# pidshield-mk-3_1.net
KiCad netlist of a schematic drawn in EAGLE
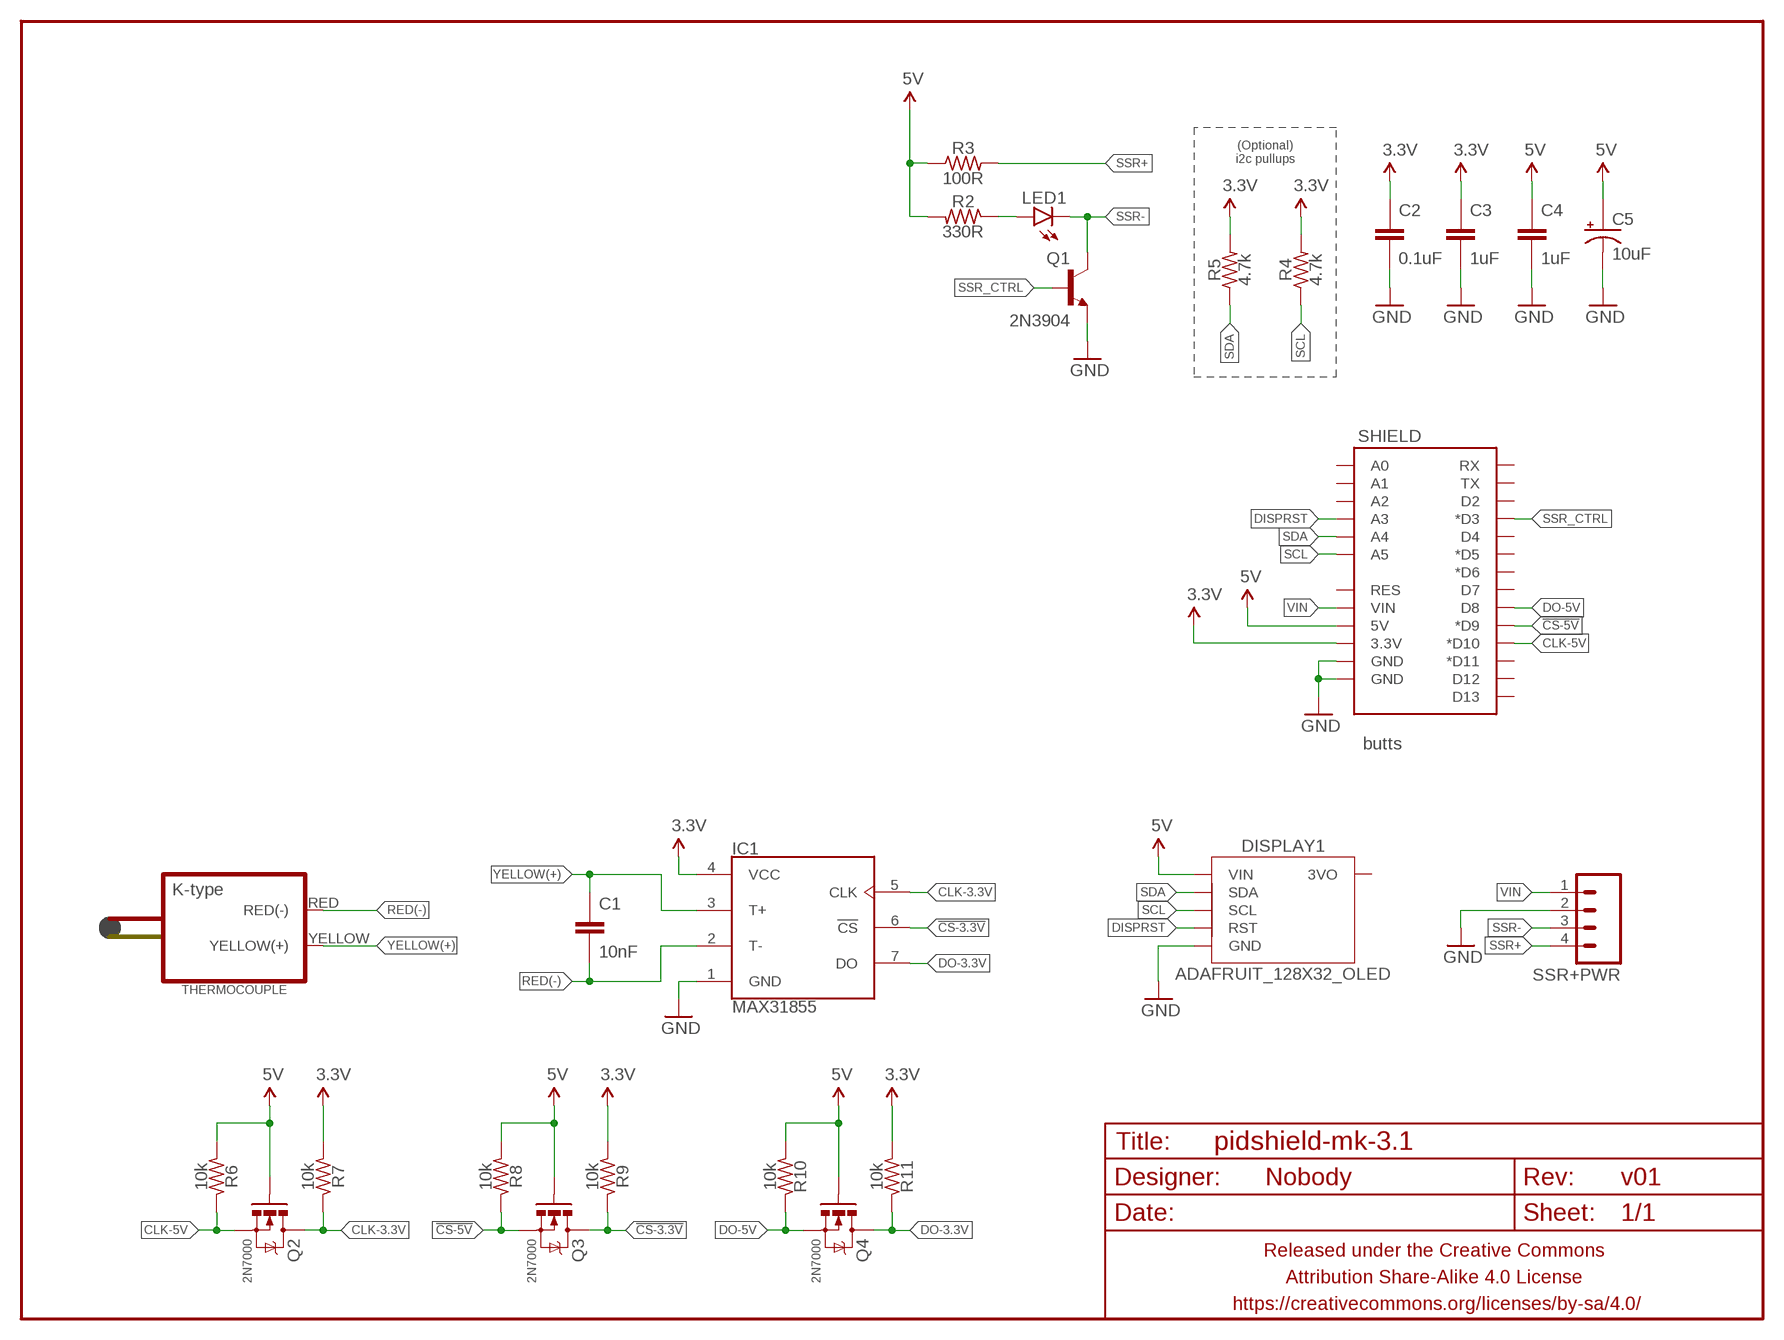
[diagram p0: schematic, sheet 1]

(export (version "E")
  (design (tool "Eeschema 10.0.6"))
  (components
    (comp (ref "C1")
      (value "10nF")
      (footprint "eagle-import:C0805")
      (libsource (lib "eagle-import") (part "CAPACITOR-CERAMICC0805"))
    )
    (comp (ref "C2")
      (value "0.1uF")
      (footprint "eagle-import:C025-024X044")
      (libsource (lib "eagle-import") (part "CAPACITOR-CERAMIC025-024X044"))
    )
    (comp (ref "C3")
      (value "1uF")
      (footprint "eagle-import:C025-024X044")
      (libsource (lib "eagle-import") (part "CAPACITOR-CERAMIC025-024X044"))
    )
    (comp (ref "C4")
      (value "1uF")
      (footprint "eagle-import:C025-024X044")
      (libsource (lib "eagle-import") (part "CAPACITOR-CERAMIC025-024X044"))
    )
    (comp (ref "C5")
      (value "10uF")
      (footprint "eagle-import:E2,5-6")
      (libsource (lib "eagle-import") (part "CAPACITOR-POLARIZEDE2.5-6"))
    )
    (comp (ref "DISPLAY1")
      (value "ADAFRUIT_128X32_OLED")
      (footprint "eagle-import:ADAFRUIT_128X32_OLED_I2C_CLOSER_NOTITLE")
      (libsource (lib "eagle-import") (part "ADAFRUIT_128X32_OLED_I2CNOTITLE"))
    )
    (comp (ref "FRAME1")
      (value "FRAME-LETTERNO_PACKAGE")
      (footprint "eagle-import:DUMMY")
      (fields (field (name "DESIGNER") "Nobody"))
      (libsource (lib "eagle-import") (part "FRAME-LETTERNO_PACKAGE"))
    )
    (comp (ref "IC1")
      (value "MAX31855")
      (footprint "eagle-import:SOIC127P600X175-8N")
      (libsource (lib "eagle-import") (part "MAX31855SOIC"))
    )
    (comp (ref "LED1")
      (value "LED3MM-LESS")
      (footprint "eagle-import:LED3MM-LESSSILK")
      (libsource (lib "eagle-import") (part "LED3MM-LESS"))
    )
    (comp (ref "Q1")
      (value "2N3904")
      (footprint "eagle-import:TO-92-AMMO")
      (libsource (lib "eagle-import") (part "TRANSISTOR_NPNTO-92-AMMO-EBC"))
    )
    (comp (ref "Q2")
      (value "2N7000")
      (footprint "eagle-import:TO-92-AMMO")
      (libsource (lib "eagle-import") (part "MOSFET-NCHANNEL2N7000-AMMO"))
    )
    (comp (ref "Q3")
      (value "2N7000")
      (footprint "eagle-import:TO-92-AMMO")
      (libsource (lib "eagle-import") (part "MOSFET-NCHANNEL2N7000-AMMO"))
    )
    (comp (ref "Q4")
      (value "2N7000")
      (footprint "eagle-import:TO-92-AMMO")
      (libsource (lib "eagle-import") (part "MOSFET-NCHANNEL2N7000-AMMO"))
    )
    (comp (ref "R2")
      (value "330R")
      (footprint "eagle-import:RESISTOR-AXIAL-PTH-7.62MM")
      (libsource (lib "eagle-import") (part "RESISTORPTH-AXIAL-7.62MM"))
    )
    (comp (ref "R3")
      (value "100R")
      (footprint "eagle-import:RESISTOR-AXIAL-PTH-7.62MM")
      (libsource (lib "eagle-import") (part "RESISTORPTH-AXIAL-7.62MM"))
    )
    (comp (ref "R4")
      (value "4.7k")
      (footprint "eagle-import:RESISTOR-AXIAL-PTH-7.62MM")
      (libsource (lib "eagle-import") (part "RESISTORPTH-AXIAL-7.62MM"))
    )
    (comp (ref "R5")
      (value "4.7k")
      (footprint "eagle-import:RESISTOR-AXIAL-PTH-7.62MM")
      (libsource (lib "eagle-import") (part "RESISTORPTH-AXIAL-7.62MM"))
    )
    (comp (ref "R6")
      (value "10k")
      (footprint "eagle-import:RESISTOR-AXIAL-PTH-7.62MM")
      (libsource (lib "eagle-import") (part "RESISTORPTH-AXIAL-7.62MM"))
    )
    (comp (ref "R7")
      (value "10k")
      (footprint "eagle-import:RESISTOR-AXIAL-PTH-7.62MM")
      (libsource (lib "eagle-import") (part "RESISTORPTH-AXIAL-7.62MM"))
    )
    (comp (ref "R8")
      (value "10k")
      (footprint "eagle-import:RESISTOR-AXIAL-PTH-7.62MM")
      (libsource (lib "eagle-import") (part "RESISTORPTH-AXIAL-7.62MM"))
    )
    (comp (ref "R9")
      (value "10k")
      (footprint "eagle-import:RESISTOR-AXIAL-PTH-7.62MM")
      (libsource (lib "eagle-import") (part "RESISTORPTH-AXIAL-7.62MM"))
    )
    (comp (ref "R10")
      (value "10k")
      (footprint "eagle-import:RESISTOR-AXIAL-PTH-7.62MM")
      (libsource (lib "eagle-import") (part "RESISTORPTH-AXIAL-7.62MM"))
    )
    (comp (ref "R11")
      (value "10k")
      (footprint "eagle-import:RESISTOR-AXIAL-PTH-7.62MM")
      (libsource (lib "eagle-import") (part "RESISTORPTH-AXIAL-7.62MM"))
    )
    (comp (ref "SHIELD")
      (value "butts")
      (footprint "eagle-import:ARDUINO_SHIELD_SMALLER_NEKKID")
      (libsource (lib "eagle-import") (part "ARDUINO_SHIELD_SMALLERNEKKID"))
    )
    (comp (ref "SSR+PWR")
      (value "M04JST_XH_RA")
      (footprint "eagle-import:JST-4-XH-RA-PTH")
      (libsource (lib "eagle-import") (part "M04JST_XH_RA"))
    )
    (comp (ref "THERMOCOUPLE")
      (value "THERMOCOUPLE-CONNECTORMINI-PCB")
      (footprint "eagle-import:PCC-SMP")
      (libsource (lib "eagle-import") (part "THERMOCOUPLE-CONNECTORMINI-PCB"))
    )
  )
  (nets
    (net (code "1") (name "/~{CS-3.3V}") (class "Default")
      (node (ref "IC1") (pin "6") (pinfunction "~{CS}_6") (pintype "input"))
      (node (ref "Q3") (pin "3") (pinfunction "D_3") (pintype "passive"))
      (node (ref "R9") (pin "P$1") (pinfunction "1_P$1") (pintype "passive"))
    )
    (net (code "2") (name "/~{CS-5V}") (class "Default")
      (node (ref "Q3") (pin "1") (pinfunction "S_1") (pintype "passive"))
      (node (ref "R8") (pin "P$1") (pinfunction "1_P$1") (pintype "passive"))
      (node (ref "SHIELD") (pin "D9") (pinfunction "*D9_D9") (pintype "bidirectional"))
    )
    (net (code "3") (name "3.3V") (class "Default")
      (node (ref "C2") (pin "1") (pinfunction "1_1") (pintype "passive"))
      (node (ref "C3") (pin "1") (pinfunction "1_1") (pintype "passive"))
      (node (ref "IC1") (pin "4") (pinfunction "VCC_4") (pintype "power_in"))
      (node (ref "R11") (pin "P$2") (pinfunction "2_P$2") (pintype "passive"))
      (node (ref "R4") (pin "P$2") (pinfunction "2_P$2") (pintype "passive"))
      (node (ref "R5") (pin "P$2") (pinfunction "2_P$2") (pintype "passive"))
      (node (ref "R7") (pin "P$2") (pinfunction "2_P$2") (pintype "passive"))
      (node (ref "R9") (pin "P$2") (pinfunction "2_P$2") (pintype "passive"))
      (node (ref "SHIELD") (pin "3.3V") (pinfunction "3.3V_3.3V") (pintype "bidirectional"))
    )
    (net (code "4") (name "5V") (class "Default")
      (node (ref "C4") (pin "1") (pinfunction "1_1") (pintype "passive"))
      (node (ref "C5") (pin "+") (pinfunction "+_+") (pintype "passive"))
      (node (ref "DISPLAY1") (pin "VIN") (pinfunction "VIN_VIN") (pintype "bidirectional"))
      (node (ref "Q2") (pin "2") (pinfunction "G_2") (pintype "passive"))
      (node (ref "Q3") (pin "2") (pinfunction "G_2") (pintype "passive"))
      (node (ref "Q4") (pin "2") (pinfunction "G_2") (pintype "passive"))
      (node (ref "R10") (pin "P$2") (pinfunction "2_P$2") (pintype "passive"))
      (node (ref "R2") (pin "P$2") (pinfunction "2_P$2") (pintype "passive"))
      (node (ref "R3") (pin "P$1") (pinfunction "1_P$1") (pintype "passive"))
      (node (ref "R6") (pin "P$2") (pinfunction "2_P$2") (pintype "passive"))
      (node (ref "R8") (pin "P$2") (pinfunction "2_P$2") (pintype "passive"))
      (node (ref "SHIELD") (pin "5V") (pinfunction "5V_5V") (pintype "bidirectional"))
    )
    (net (code "5") (name "CLK-3.3V") (class "Default")
      (node (ref "IC1") (pin "5") (pinfunction "CLK_5") (pintype "input"))
      (node (ref "Q2") (pin "3") (pinfunction "D_3") (pintype "passive"))
      (node (ref "R7") (pin "P$1") (pinfunction "1_P$1") (pintype "passive"))
    )
    (net (code "6") (name "CLK-5V") (class "Default")
      (node (ref "Q2") (pin "1") (pinfunction "S_1") (pintype "passive"))
      (node (ref "R6") (pin "P$1") (pinfunction "1_P$1") (pintype "passive"))
      (node (ref "SHIELD") (pin "D10") (pinfunction "*D10_D10") (pintype "bidirectional"))
    )
    (net (code "7") (name "DISPRST") (class "Default")
      (node (ref "DISPLAY1") (pin "RST") (pinfunction "RST_RST") (pintype "bidirectional"))
      (node (ref "SHIELD") (pin "A3") (pinfunction "A3_A3") (pintype "bidirectional"))
    )
    (net (code "8") (name "DO-3.3V") (class "Default")
      (node (ref "IC1") (pin "7") (pinfunction "DO_7") (pintype "output"))
      (node (ref "Q4") (pin "3") (pinfunction "D_3") (pintype "passive"))
      (node (ref "R11") (pin "P$1") (pinfunction "1_P$1") (pintype "passive"))
    )
    (net (code "9") (name "DO-5V") (class "Default")
      (node (ref "Q4") (pin "1") (pinfunction "S_1") (pintype "passive"))
      (node (ref "R10") (pin "P$1") (pinfunction "1_P$1") (pintype "passive"))
      (node (ref "SHIELD") (pin "D8") (pinfunction "D8_D8") (pintype "bidirectional"))
    )
    (net (code "10") (name "GND") (class "Default")
      (node (ref "C2") (pin "2") (pinfunction "2_2") (pintype "passive"))
      (node (ref "C3") (pin "2") (pinfunction "2_2") (pintype "passive"))
      (node (ref "C4") (pin "2") (pinfunction "2_2") (pintype "passive"))
      (node (ref "C5") (pin "-") (pinfunction "-_-") (pintype "passive"))
      (node (ref "DISPLAY1") (pin "GND") (pinfunction "GND_GND") (pintype "bidirectional"))
      (node (ref "IC1") (pin "1") (pinfunction "GND_1") (pintype "power_in"))
      (node (ref "Q1") (pin "1") (pinfunction "E_1") (pintype "passive"))
      (node (ref "SHIELD") (pin "GND@0") (pinfunction "GND_GND@0") (pintype "bidirectional"))
      (node (ref "SHIELD") (pin "GND@1") (pinfunction "GND_GND@1") (pintype "bidirectional"))
      (node (ref "SSR+PWR") (pin "2") (pinfunction "2_2") (pintype "passive"))
    )
    (net (code "11") (name "Net-(R2-1)") (class "Default")
      (node (ref "LED1") (pin "A") (pinfunction "A_A") (pintype "passive"))
      (node (ref "R2") (pin "P$1") (pinfunction "1_P$1") (pintype "passive"))
    )
    (net (code "12") (name "RED(-)") (class "Default")
      (node (ref "C1") (pin "2") (pinfunction "2_2") (pintype "passive"))
      (node (ref "IC1") (pin "2") (pinfunction "T-_2") (pintype "input"))
      (node (ref "THERMOCOUPLE") (pin "RED") (pinfunction "RED(-)_RED") (pintype "bidirectional"))
    )
    (net (code "13") (name "SCL") (class "Default")
      (node (ref "DISPLAY1") (pin "SCL") (pinfunction "SCL_SCL") (pintype "bidirectional"))
      (node (ref "R4") (pin "P$1") (pinfunction "1_P$1") (pintype "passive"))
      (node (ref "SHIELD") (pin "A5") (pinfunction "A5_A5") (pintype "bidirectional"))
    )
    (net (code "14") (name "SDA") (class "Default")
      (node (ref "DISPLAY1") (pin "SDA") (pinfunction "SDA_SDA") (pintype "bidirectional"))
      (node (ref "R5") (pin "P$1") (pinfunction "1_P$1") (pintype "passive"))
      (node (ref "SHIELD") (pin "A4") (pinfunction "A4_A4") (pintype "bidirectional"))
    )
    (net (code "15") (name "SSR+") (class "Default")
      (node (ref "R3") (pin "P$2") (pinfunction "2_P$2") (pintype "passive"))
      (node (ref "SSR+PWR") (pin "4") (pinfunction "4_4") (pintype "passive"))
    )
    (net (code "16") (name "SSR-") (class "Default")
      (node (ref "LED1") (pin "K") (pinfunction "C_K") (pintype "passive"))
      (node (ref "Q1") (pin "3") (pinfunction "C_3") (pintype "passive"))
      (node (ref "SSR+PWR") (pin "3") (pinfunction "3_3") (pintype "passive"))
    )
    (net (code "17") (name "SSR_CTRL") (class "Default")
      (node (ref "Q1") (pin "2") (pinfunction "B_2") (pintype "passive"))
      (node (ref "SHIELD") (pin "D3") (pinfunction "*D3_D3") (pintype "bidirectional"))
    )
    (net (code "18") (name "VIN") (class "Default")
      (node (ref "SHIELD") (pin "VIN") (pinfunction "VIN_VIN") (pintype "bidirectional"))
      (node (ref "SSR+PWR") (pin "1") (pinfunction "1_1") (pintype "passive"))
    )
    (net (code "19") (name "YELLOW(+)") (class "Default")
      (node (ref "C1") (pin "1") (pinfunction "1_1") (pintype "passive"))
      (node (ref "IC1") (pin "3") (pinfunction "T+_3") (pintype "input"))
      (node (ref "THERMOCOUPLE") (pin "YELLOW") (pinfunction "YELLOW(+)_YELLOW") (pintype "bidirectional"))
    )
    (net (code "20") (name "unconnected-(DISPLAY1-Pad3VO)") (class "Default")
      (node (ref "DISPLAY1") (pin "3VO") (pinfunction "3VO_3VO") (pintype "bidirectional"))
    )
    (net (code "21") (name "unconnected-(SHIELD-*D5-PadD5)") (class "Default")
      (node (ref "SHIELD") (pin "D5") (pinfunction "*D5_D5") (pintype "bidirectional"))
    )
    (net (code "22") (name "unconnected-(SHIELD-*D6-PadD6)") (class "Default")
      (node (ref "SHIELD") (pin "D6") (pinfunction "*D6_D6") (pintype "bidirectional"))
    )
    (net (code "23") (name "unconnected-(SHIELD-*D11-PadD11)") (class "Default")
      (node (ref "SHIELD") (pin "D11") (pinfunction "*D11_D11") (pintype "bidirectional"))
    )
    (net (code "24") (name "unconnected-(SHIELD-PadA0)") (class "Default")
      (node (ref "SHIELD") (pin "A0") (pinfunction "A0_A0") (pintype "bidirectional"))
    )
    (net (code "25") (name "unconnected-(SHIELD-PadA1)") (class "Default")
      (node (ref "SHIELD") (pin "A1") (pinfunction "A1_A1") (pintype "bidirectional"))
    )
    (net (code "26") (name "unconnected-(SHIELD-PadA2)") (class "Default")
      (node (ref "SHIELD") (pin "A2") (pinfunction "A2_A2") (pintype "bidirectional"))
    )
    (net (code "27") (name "unconnected-(SHIELD-PadD2)") (class "Default")
      (node (ref "SHIELD") (pin "D2") (pinfunction "D2_D2") (pintype "bidirectional"))
    )
    (net (code "28") (name "unconnected-(SHIELD-PadD4)") (class "Default")
      (node (ref "SHIELD") (pin "D4") (pinfunction "D4_D4") (pintype "bidirectional"))
    )
    (net (code "29") (name "unconnected-(SHIELD-PadD7)") (class "Default")
      (node (ref "SHIELD") (pin "D7") (pinfunction "D7_D7") (pintype "bidirectional"))
    )
    (net (code "30") (name "unconnected-(SHIELD-PadD12)") (class "Default")
      (node (ref "SHIELD") (pin "D12") (pinfunction "D12_D12") (pintype "bidirectional"))
    )
    (net (code "31") (name "unconnected-(SHIELD-PadD13)") (class "Default")
      (node (ref "SHIELD") (pin "D13") (pinfunction "D13_D13") (pintype "bidirectional"))
    )
    (net (code "32") (name "unconnected-(SHIELD-PadRES)") (class "Default")
      (node (ref "SHIELD") (pin "RES") (pinfunction "RES_RES") (pintype "bidirectional"))
    )
    (net (code "33") (name "unconnected-(SHIELD-PadRX)") (class "Default")
      (node (ref "SHIELD") (pin "RX") (pinfunction "RX_RX") (pintype "bidirectional"))
    )
    (net (code "34") (name "unconnected-(SHIELD-PadTX)") (class "Default")
      (node (ref "SHIELD") (pin "TX") (pinfunction "TX_TX") (pintype "bidirectional"))
    )
  )
)
